# device.net
KiCad netlist of a schematic drawn in EAGLE
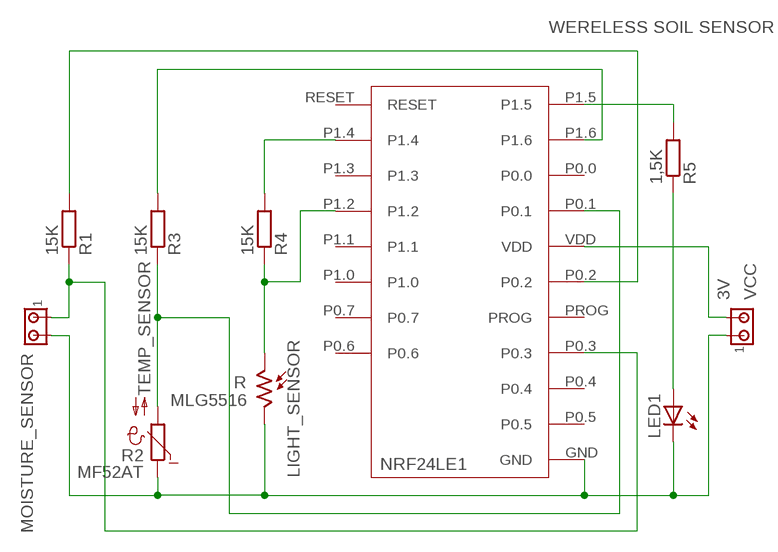
[diagram p0: schematic, sheet 1]

(export (version "E")
  (design (tool "Eeschema 10.0.6"))
  (components
    (comp (ref "LED1")
      (value "LEDCHIP-LED0805")
      (footprint "eagle-import:CHIP-LED0805")
      (libsource (lib "eagle-import") (part "LEDCHIP-LED0805"))
    )
    (comp (ref "MOISTURE_SENSOR")
      (value "MTA02-100")
      (footprint "eagle-import:10X02MTA")
      (libsource (lib "eagle-import") (part "MTA02-100"))
    )
    (comp (ref "NRF")
      (value "NRF24LE1")
      (footprint "eagle-import:NRF24LE1")
      (libsource (lib "eagle-import") (part "NRF24LE1"))
    )
    (comp (ref "R")
      (value "MLG5516")
      (footprint "eagle-import:T0-46-A10XX")
      (libsource (lib "eagle-import") (part "A1050_09"))
    )
    (comp (ref "R1")
      (value "15K")
      (footprint "eagle-import:R1206")
      (libsource (lib "eagle-import") (part "R-EU_R1206"))
    )
    (comp (ref "R2")
      (value "MF52AT")
      (footprint "eagle-import:P640")
      (libsource (lib "eagle-import") (part "NTC640"))
    )
    (comp (ref "R3")
      (value "15K")
      (footprint "eagle-import:R1206")
      (libsource (lib "eagle-import") (part "R-EU_R1206"))
    )
    (comp (ref "R4")
      (value "15K")
      (footprint "eagle-import:R1206")
      (libsource (lib "eagle-import") (part "R-EU_R1206"))
    )
    (comp (ref "R5")
      (value "1,5K")
      (footprint "eagle-import:R1206")
      (libsource (lib "eagle-import") (part "R-EU_R1206"))
    )
    (comp (ref "VCC")
      (value "3V")
      (footprint "eagle-import:10X02MTA")
      (libsource (lib "eagle-import") (part "MTA02-100"))
    )
  )
  (nets
    (net (code "1") (name "Net-(LED1-PadA)") (class "Default")
      (node (ref "LED1") (pin "A") (pinfunction "A_A") (pintype "passive"))
      (node (ref "R5") (pin "1") (pinfunction "1_1") (pintype "passive"))
    )
    (net (code "2") (name "Net-(LED1-PadC)") (class "Default")
      (node (ref "LED1") (pin "C") (pinfunction "C_C") (pintype "passive"))
      (node (ref "MOISTURE_SENSOR") (pin "2") (pinfunction "2_2") (pintype "passive"))
      (node (ref "NRF") (pin "GND") (pinfunction "GND_GND") (pintype "power_in"))
      (node (ref "R") (pin "2") (pinfunction "2_2") (pintype "passive"))
      (node (ref "R2") (pin "1") (pinfunction "1_1") (pintype "passive"))
      (node (ref "VCC") (pin "1") (pinfunction "1_1") (pintype "passive"))
    )
    (net (code "3") (name "Net-(MOISTURE_SENSOR-Pad1)") (class "Default")
      (node (ref "MOISTURE_SENSOR") (pin "1") (pinfunction "1_1") (pintype "passive"))
      (node (ref "NRF") (pin "P0.3") (pinfunction "P0.3_P0.3") (pintype "bidirectional"))
      (node (ref "R1") (pin "1") (pinfunction "1_1") (pintype "passive"))
    )
    (net (code "4") (name "Net-(NRF-PadP0.1)") (class "Default")
      (node (ref "NRF") (pin "P0.1") (pinfunction "P0.1_P0.1") (pintype "bidirectional"))
      (node (ref "R2") (pin "2") (pinfunction "2_2") (pintype "passive"))
      (node (ref "R3") (pin "1") (pinfunction "1_1") (pintype "passive"))
    )
    (net (code "5") (name "Net-(NRF-PadP0.2)") (class "Default")
      (node (ref "NRF") (pin "P0.2") (pinfunction "P0.2_P0.2") (pintype "bidirectional"))
      (node (ref "R1") (pin "2") (pinfunction "2_2") (pintype "passive"))
    )
    (net (code "6") (name "Net-(NRF-PadP1.2)") (class "Default")
      (node (ref "NRF") (pin "P1.2") (pinfunction "P1.2_P1.2") (pintype "bidirectional"))
      (node (ref "R") (pin "1") (pinfunction "1_1") (pintype "passive"))
      (node (ref "R4") (pin "1") (pinfunction "1_1") (pintype "passive"))
    )
    (net (code "7") (name "Net-(NRF-PadP1.4)") (class "Default")
      (node (ref "NRF") (pin "P1.4") (pinfunction "P1.4_P1.4") (pintype "bidirectional"))
      (node (ref "R4") (pin "2") (pinfunction "2_2") (pintype "passive"))
    )
    (net (code "8") (name "Net-(NRF-PadP1.5)") (class "Default")
      (node (ref "NRF") (pin "P1.5") (pinfunction "P1.5_P1.5") (pintype "bidirectional"))
      (node (ref "R5") (pin "2") (pinfunction "2_2") (pintype "passive"))
    )
    (net (code "9") (name "Net-(NRF-PadP1.6)") (class "Default")
      (node (ref "NRF") (pin "P1.6") (pinfunction "P1.6_P1.6") (pintype "bidirectional"))
      (node (ref "R3") (pin "2") (pinfunction "2_2") (pintype "passive"))
    )
    (net (code "10") (name "Net-(NRF-PadVDD)") (class "Default")
      (node (ref "NRF") (pin "VDD") (pinfunction "VDD_VDD") (pintype "power_in"))
      (node (ref "VCC") (pin "2") (pinfunction "2_2") (pintype "passive"))
    )
    (net (code "11") (name "unconnected-(NRF-PadP0.0)") (class "Default")
      (node (ref "NRF") (pin "P0.0") (pinfunction "P0.0_P0.0") (pintype "bidirectional"))
    )
    (net (code "12") (name "unconnected-(NRF-PadP0.4)") (class "Default")
      (node (ref "NRF") (pin "P0.4") (pinfunction "P0.4_P0.4") (pintype "bidirectional"))
    )
    (net (code "13") (name "unconnected-(NRF-PadP0.5)") (class "Default")
      (node (ref "NRF") (pin "P0.5") (pinfunction "P0.5_P0.5") (pintype "bidirectional"))
    )
    (net (code "14") (name "unconnected-(NRF-PadP0.6)") (class "Default")
      (node (ref "NRF") (pin "P0.6") (pinfunction "P0.6_P0.6") (pintype "bidirectional"))
    )
    (net (code "15") (name "unconnected-(NRF-PadP0.7)") (class "Default")
      (node (ref "NRF") (pin "P0.7") (pinfunction "P0.7_P0.7") (pintype "bidirectional"))
    )
    (net (code "16") (name "unconnected-(NRF-PadP1.0)") (class "Default")
      (node (ref "NRF") (pin "P1.0") (pinfunction "P1.0_P1.0") (pintype "bidirectional"))
    )
    (net (code "17") (name "unconnected-(NRF-PadP1.1)") (class "Default")
      (node (ref "NRF") (pin "P1.1") (pinfunction "P1.1_P1.1") (pintype "bidirectional"))
    )
    (net (code "18") (name "unconnected-(NRF-PadP1.3)") (class "Default")
      (node (ref "NRF") (pin "P1.3") (pinfunction "P1.3_P1.3") (pintype "bidirectional"))
    )
    (net (code "19") (name "unconnected-(NRF-PadPROG)") (class "Default")
      (node (ref "NRF") (pin "PROG") (pinfunction "PROG_PROG") (pintype "bidirectional"))
    )
    (net (code "20") (name "unconnected-(NRF-PadRESET)") (class "Default")
      (node (ref "NRF") (pin "RESET") (pinfunction "RESET_RESET") (pintype "bidirectional"))
    )
  )
)
